# design.net
KiCad netlist of a schematic drawn in EasyEDA Pro
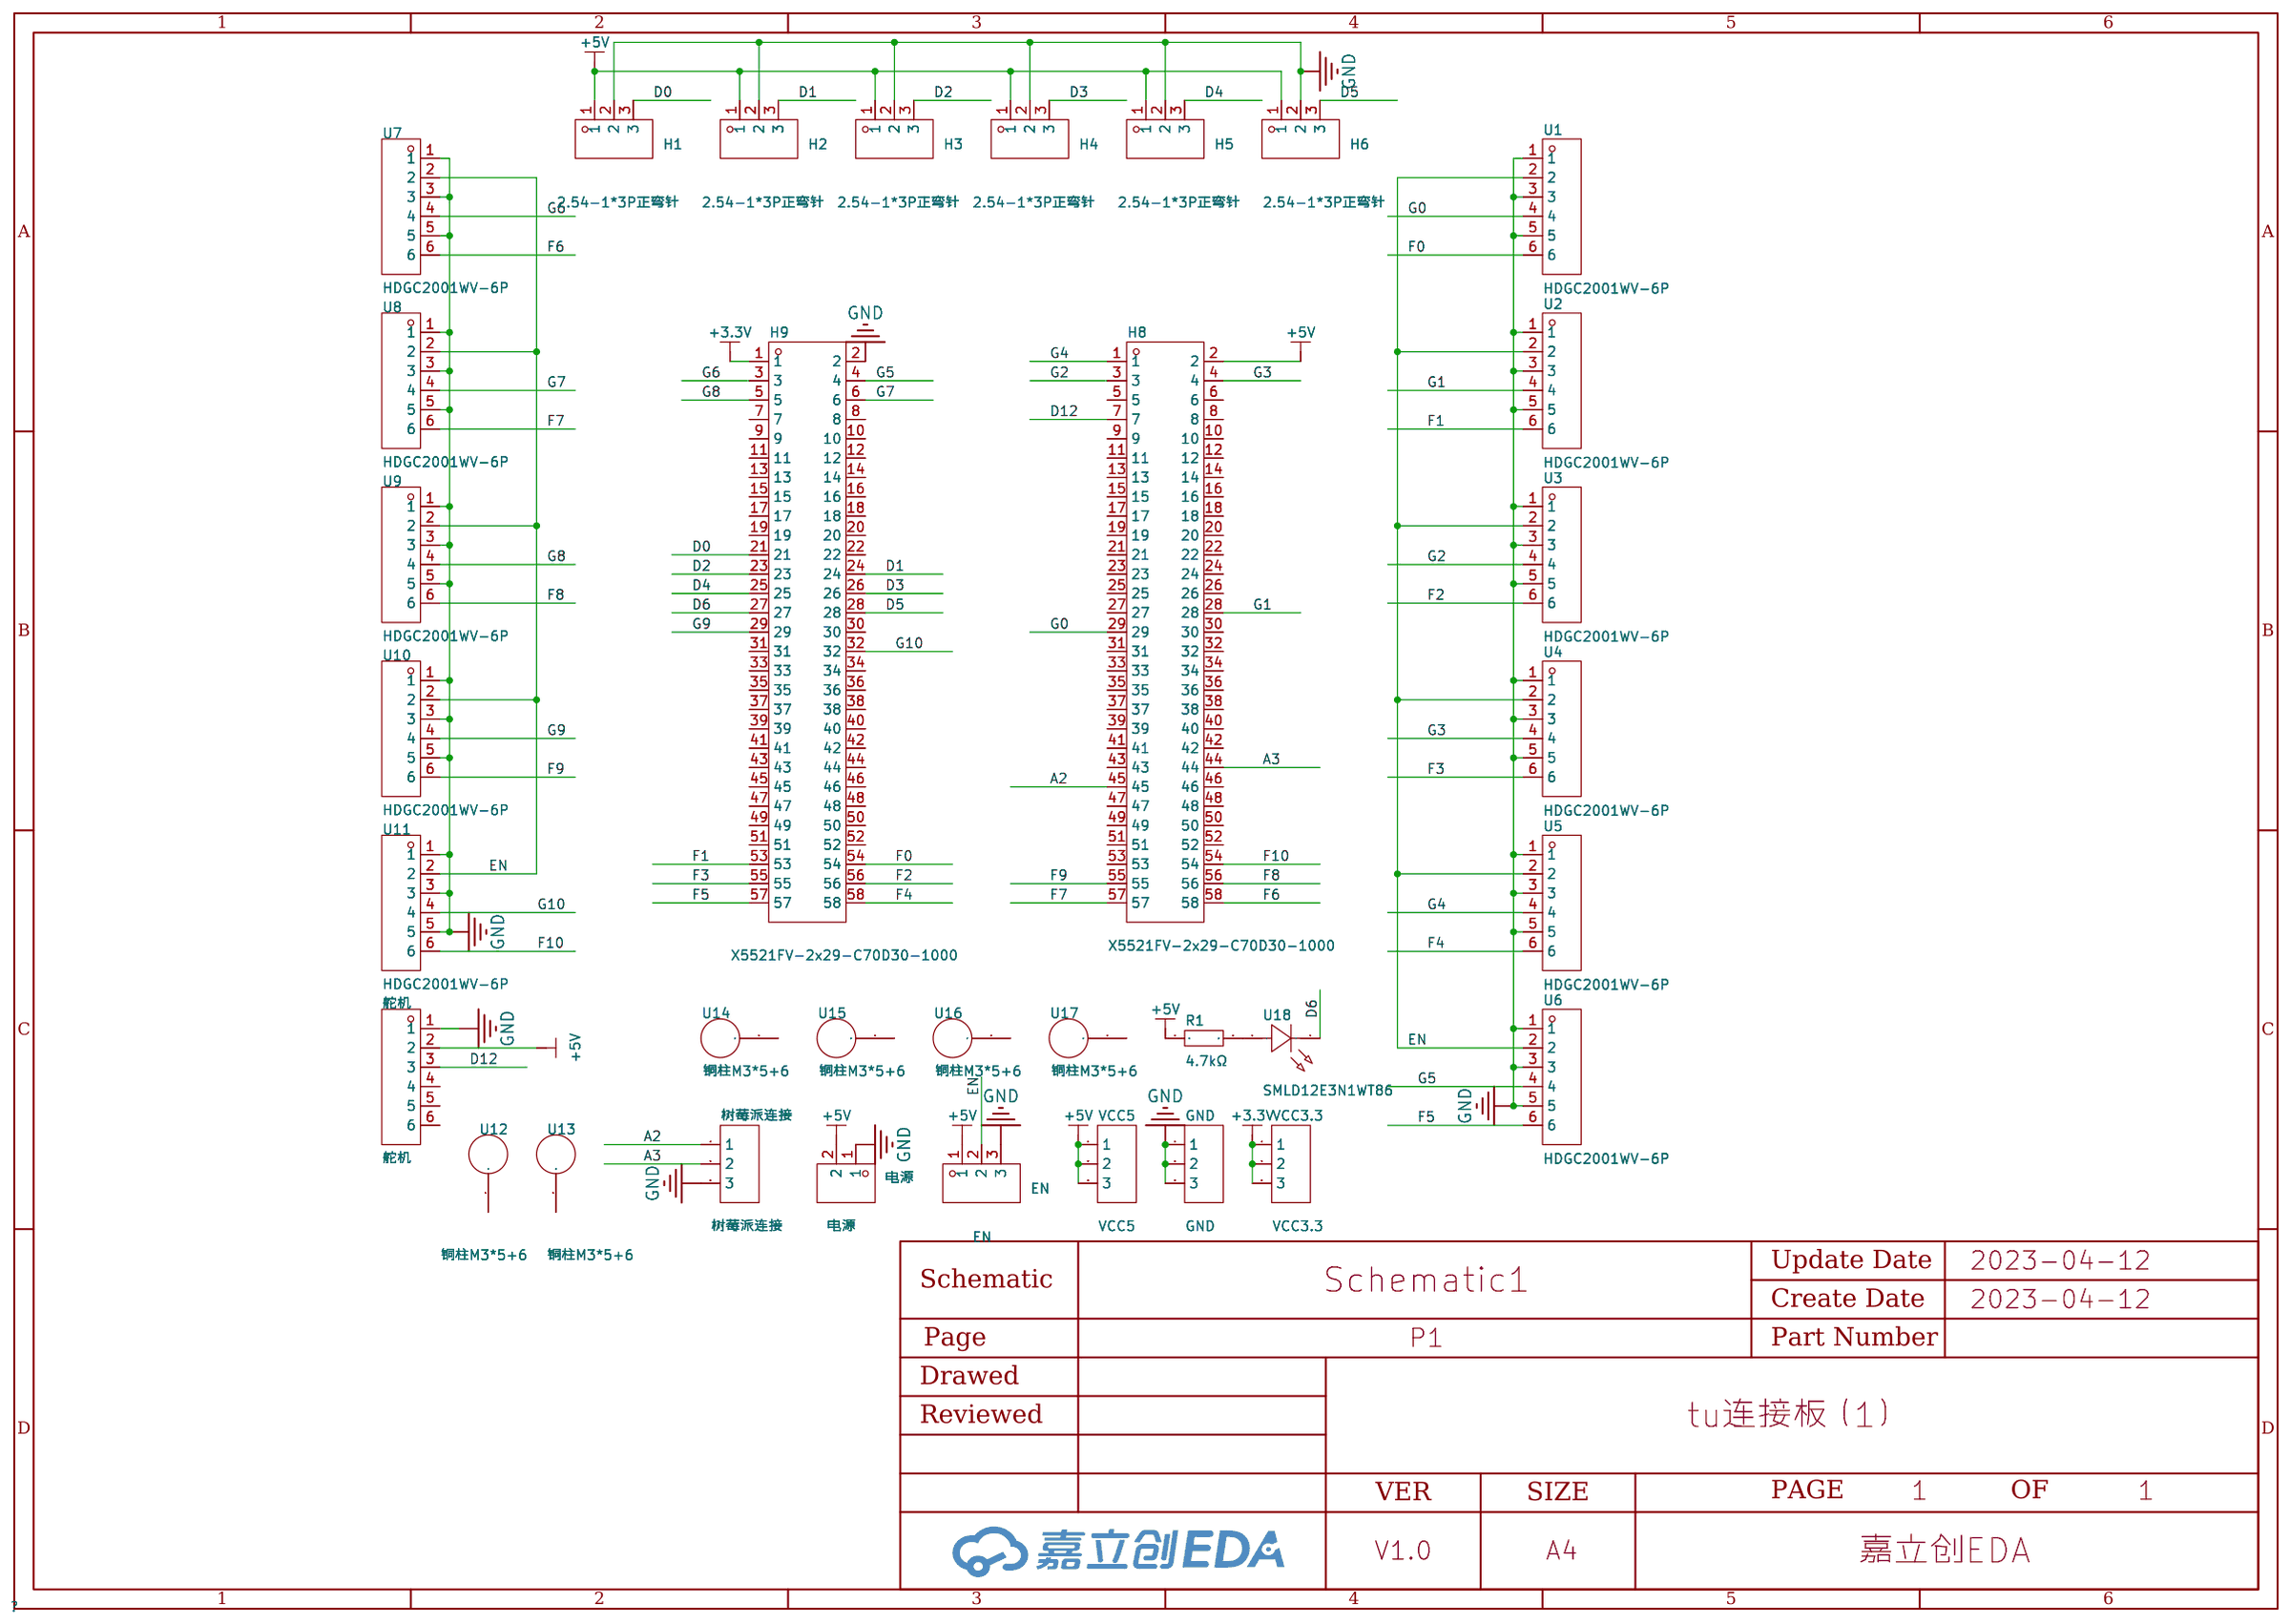
[diagram p0: schematic sheet]

(export (version "E")
  (design (tool "Eeschema 10.0.6"))
  (components
    (comp (ref "EN")
      (value "EN")
      (footprint "easyedapro:HDR-TH_3P-P2.54-H-M-BW7.2-P")
      (fields (field (name "Manufacturer Part") "2.54-1*3P正弯针") (field (name "Manufacturer") "BOOMELE(博穆精密)"))
      (libsource (lib "easyedapro") (part "C92159"))
    )
    (comp (ref "GND")
      (value "GND")
      (footprint "easyedapro:HDR-TH_3P-P2.54-V-M-1")
      (fields (field (name "Manufacturer Part") "2.54-1*3P针") (field (name "Manufacturer") "BOOMELE(博穆精密)"))
      (libsource (lib "easyedapro") (part "Header-Male-2.54_1x3"))
    )
    (comp (ref "H1")
      (value "2.54-1*3P正弯针")
      (footprint "easyedapro:HDR-TH_3P-P2.54-H-M-BW7.2-P")
      (fields (field (name "Manufacturer") "BOOMELE(博穆精密)"))
      (libsource (lib "easyedapro") (part "C92159"))
    )
    (comp (ref "H2")
      (value "2.54-1*3P正弯针")
      (footprint "easyedapro:HDR-TH_3P-P2.54-H-M-BW7.2-P")
      (fields (field (name "Manufacturer") "BOOMELE(博穆精密)"))
      (libsource (lib "easyedapro") (part "C92159"))
    )
    (comp (ref "H3")
      (value "2.54-1*3P正弯针")
      (footprint "easyedapro:HDR-TH_3P-P2.54-H-M-BW7.2-P")
      (fields (field (name "Manufacturer") "BOOMELE(博穆精密)"))
      (libsource (lib "easyedapro") (part "C92159"))
    )
    (comp (ref "H4")
      (value "2.54-1*3P正弯针")
      (footprint "easyedapro:HDR-TH_3P-P2.54-H-M-BW7.2-P")
      (fields (field (name "Manufacturer") "BOOMELE(博穆精密)"))
      (libsource (lib "easyedapro") (part "C92159"))
    )
    (comp (ref "H5")
      (value "2.54-1*3P正弯针")
      (footprint "easyedapro:HDR-TH_3P-P2.54-H-M-BW7.2-P")
      (fields (field (name "Manufacturer") "BOOMELE(博穆精密)"))
      (libsource (lib "easyedapro") (part "C92159"))
    )
    (comp (ref "H6")
      (value "2.54-1*3P正弯针")
      (footprint "easyedapro:HDR-TH_3P-P2.54-H-M-BW7.2-P")
      (fields (field (name "Manufacturer") "BOOMELE(博穆精密)"))
      (libsource (lib "easyedapro") (part "C92159"))
    )
    (comp (ref "H8")
      (value "X5521FV-2x29-C70D30-1000")
      (footprint "easyedapro:HDR-TH_58P-P2.54-V-F-R2-C29-S2.54")
      (fields (field (name "Manufacturer") "XKB Connectivity(中国星坤)"))
      (libsource (lib "easyedapro") (part "X5521FV-2X29-C70D30-1000"))
    )
    (comp (ref "H9")
      (value "X5521FV-2x29-C70D30-1000")
      (footprint "easyedapro:HDR-TH_58P-P2.54-V-F-R2-C29-S2.54")
      (fields (field (name "Manufacturer") "XKB Connectivity(中国星坤)"))
      (libsource (lib "easyedapro") (part "X5521FV-2X29-C70D30-1000"))
    )
    (comp (ref "R1")
      (value "4.7kΩ")
      (footprint "easyedapro:R0603")
      (description "电阻类型:厚膜电阻;阻值:10kΩ;精度:±1%;功率:100mW;")
      (fields
        (field (name "Manufacturer Part") "0603WAF1002T5E")
        (field (name "Manufacturer") "UNI-ROYAL(厚声)")
      )
      (libsource (lib "easyedapro") (part "0603WAF1002T5E"))
    )
    (comp (ref "U1")
      (value "HDGC2001WV-6P")
      (footprint "easyedapro:CONN-TH_6P-P2.00_HDGC2001WV-6P")
      (fields (field (name "Manufacturer") "HDGC(华德共创)"))
      (libsource (lib "easyedapro") (part "HDGC2001WV-6P"))
    )
    (comp (ref "U2")
      (value "HDGC2001WV-6P")
      (footprint "easyedapro:CONN-TH_6P-P2.00_HDGC2001WV-6P")
      (fields (field (name "Manufacturer") "HDGC(华德共创)"))
      (libsource (lib "easyedapro") (part "HDGC2001WV-6P"))
    )
    (comp (ref "U3")
      (value "HDGC2001WV-6P")
      (footprint "easyedapro:CONN-TH_6P-P2.00_HDGC2001WV-6P")
      (fields (field (name "Manufacturer") "HDGC(华德共创)"))
      (libsource (lib "easyedapro") (part "HDGC2001WV-6P"))
    )
    (comp (ref "U4")
      (value "HDGC2001WV-6P")
      (footprint "easyedapro:CONN-TH_6P-P2.00_HDGC2001WV-6P")
      (fields (field (name "Manufacturer") "HDGC(华德共创)"))
      (libsource (lib "easyedapro") (part "HDGC2001WV-6P"))
    )
    (comp (ref "U5")
      (value "HDGC2001WV-6P")
      (footprint "easyedapro:CONN-TH_6P-P2.00_HDGC2001WV-6P")
      (fields (field (name "Manufacturer") "HDGC(华德共创)"))
      (libsource (lib "easyedapro") (part "HDGC2001WV-6P"))
    )
    (comp (ref "U6")
      (value "HDGC2001WV-6P")
      (footprint "easyedapro:CONN-TH_6P-P2.00_HDGC2001WV-6P")
      (fields (field (name "Manufacturer") "HDGC(华德共创)"))
      (libsource (lib "easyedapro") (part "HDGC2001WV-6P"))
    )
    (comp (ref "U7")
      (value "HDGC2001WV-6P")
      (footprint "easyedapro:CONN-TH_6P-P2.00_HDGC2001WV-6P")
      (fields (field (name "Manufacturer") "HDGC(华德共创)"))
      (libsource (lib "easyedapro") (part "HDGC2001WV-6P"))
    )
    (comp (ref "U8")
      (value "HDGC2001WV-6P")
      (footprint "easyedapro:CONN-TH_6P-P2.00_HDGC2001WV-6P")
      (fields (field (name "Manufacturer") "HDGC(华德共创)"))
      (libsource (lib "easyedapro") (part "HDGC2001WV-6P"))
    )
    (comp (ref "U9")
      (value "HDGC2001WV-6P")
      (footprint "easyedapro:CONN-TH_6P-P2.00_HDGC2001WV-6P")
      (fields (field (name "Manufacturer") "HDGC(华德共创)"))
      (libsource (lib "easyedapro") (part "HDGC2001WV-6P"))
    )
    (comp (ref "U10")
      (value "HDGC2001WV-6P")
      (footprint "easyedapro:CONN-TH_6P-P2.00_HDGC2001WV-6P")
      (fields (field (name "Manufacturer") "HDGC(华德共创)"))
      (libsource (lib "easyedapro") (part "HDGC2001WV-6P"))
    )
    (comp (ref "U11")
      (value "HDGC2001WV-6P")
      (footprint "easyedapro:CONN-TH_6P-P2.00_HDGC2001WV-6P")
      (fields (field (name "Manufacturer") "HDGC(华德共创)"))
      (libsource (lib "easyedapro") (part "HDGC2001WV-6P"))
    )
    (comp (ref "U12")
      (value "铜柱M3*5+6")
      (footprint "easyedapro:SMD_BD4.2-L4.7-W4.7-D3.0")
      (description "螺柱类型:单通螺柱;公称直径:M3;螺距:-;长度:11mm;执行标准:-;强度等级:-;材料:-;表面处理:-;")
      (fields (field (name "Manufacturer") "国产"))
      (libsource (lib "easyedapro") (part "铜柱M3*5+6"))
    )
    (comp (ref "U13")
      (value "铜柱M3*5+6")
      (footprint "easyedapro:SMD_BD4.2-L4.7-W4.7-D3.0")
      (description "螺柱类型:单通螺柱;公称直径:M3;螺距:-;长度:11mm;执行标准:-;强度等级:-;材料:-;表面处理:-;")
      (fields (field (name "Manufacturer") "国产"))
      (libsource (lib "easyedapro") (part "铜柱M3*5+6"))
    )
    (comp (ref "U14")
      (value "铜柱M3*5+6")
      (footprint "easyedapro:SMD_BD4.2-L4.7-W4.7-D3.0")
      (description "螺柱类型:单通螺柱;公称直径:M3;螺距:-;长度:11mm;执行标准:-;强度等级:-;材料:-;表面处理:-;")
      (fields (field (name "Manufacturer") "国产"))
      (libsource (lib "easyedapro") (part "铜柱M3*5+6"))
    )
    (comp (ref "U15")
      (value "铜柱M3*5+6")
      (footprint "easyedapro:SMD_BD4.2-L4.7-W4.7-D3.0")
      (description "螺柱类型:单通螺柱;公称直径:M3;螺距:-;长度:11mm;执行标准:-;强度等级:-;材料:-;表面处理:-;")
      (fields (field (name "Manufacturer") "国产"))
      (libsource (lib "easyedapro") (part "铜柱M3*5+6"))
    )
    (comp (ref "U16")
      (value "铜柱M3*5+6")
      (footprint "easyedapro:SMD_BD4.2-L4.7-W4.7-D3.0")
      (description "螺柱类型:单通螺柱;公称直径:M3;螺距:-;长度:11mm;执行标准:-;强度等级:-;材料:-;表面处理:-;")
      (fields (field (name "Manufacturer") "国产"))
      (libsource (lib "easyedapro") (part "铜柱M3*5+6"))
    )
    (comp (ref "U17")
      (value "铜柱M3*5+6")
      (footprint "easyedapro:SMD_BD4.2-L4.7-W4.7-D3.0")
      (description "螺柱类型:单通螺柱;公称直径:M3;螺距:-;长度:11mm;执行标准:-;强度等级:-;材料:-;表面处理:-;")
      (fields (field (name "Manufacturer") "国产"))
      (libsource (lib "easyedapro") (part "铜柱M3*5+6"))
    )
    (comp (ref "U18")
      (value "SMLD12E3N1WT86")
      (footprint "easyedapro:LED-SMD_L1.6-W0.8-RD")
      (fields (field (name "Manufacturer") "ROHM(罗姆)"))
      (libsource (lib "easyedapro") (part "SMLD12E3N1WT86"))
    )
    (comp (ref "VCC3.3")
      (value "VCC3.3")
      (footprint "easyedapro:HDR-TH_3P-P2.54-V-M-1")
      (fields (field (name "Manufacturer Part") "2.54-1*3P针") (field (name "Manufacturer") "BOOMELE(博穆精密)"))
      (libsource (lib "easyedapro") (part "Header-Male-2.54_1x3"))
    )
    (comp (ref "VCC5")
      (value "VCC5")
      (footprint "easyedapro:HDR-TH_3P-P2.54-V-M-1")
      (fields (field (name "Manufacturer Part") "2.54-1*3P针") (field (name "Manufacturer") "BOOMELE(博穆精密)"))
      (libsource (lib "easyedapro") (part "Header-Male-2.54_1x3"))
    )
    (comp (ref "树莓派连接")
      (value "树莓派连接")
      (footprint "easyedapro:HDR-TH_3P-P2.54-V-M-1")
      (fields (field (name "Manufacturer Part") "2.54-1*3P针") (field (name "Manufacturer") "BOOMELE(博穆精密)"))
      (libsource (lib "easyedapro") (part "Header-Male-2.54_1x3"))
    )
    (comp (ref "电源")
      (value "电源")
      (footprint "easyedapro:CONN-TH_XHB-2A_C2829622")
      (fields (field (name "Manufacturer Part") "XHB-2A") (field (name "Manufacturer") "FG(富港)"))
      (libsource (lib "easyedapro") (part "XHB-2A_C2829622"))
    )
    (comp (ref "舵机")
      (value "舵机")
      (footprint "easyedapro:CONN-TH_6P-P2.00_HDGC2001WV-6P")
      (fields (field (name "Manufacturer Part") "HDGC2001WV-6P") (field (name "Manufacturer") "HDGC(华德共创)"))
      (libsource (lib "easyedapro") (part "HDGC2001WV-6P"))
    )
  )
  (nets
    (net (code "1") (name "+3.3V") (class "Default")
      (node (ref "H9") (pin "1") (pinfunction "1_1") (pintype "input"))
      (node (ref "VCC3.3") (pin "1") (pinfunction "1_1") (pintype "input"))
      (node (ref "VCC3.3") (pin "2") (pinfunction "2_2") (pintype "input"))
      (node (ref "VCC3.3") (pin "3") (pinfunction "3_3") (pintype "input"))
    )
    (net (code "2") (name "+5V") (class "Default")
      (node (ref "EN") (pin "1") (pinfunction "1_1") (pintype "input"))
      (node (ref "H1") (pin "1") (pinfunction "1_1") (pintype "input"))
      (node (ref "H2") (pin "1") (pinfunction "1_1") (pintype "input"))
      (node (ref "H3") (pin "1") (pinfunction "1_1") (pintype "input"))
      (node (ref "H4") (pin "1") (pinfunction "1_1") (pintype "input"))
      (node (ref "H5") (pin "1") (pinfunction "1_1") (pintype "input"))
      (node (ref "H6") (pin "1") (pinfunction "1_1") (pintype "input"))
      (node (ref "H8") (pin "2") (pinfunction "2_2") (pintype "input"))
      (node (ref "R1") (pin "1") (pinfunction "1_1") (pintype "input"))
      (node (ref "VCC5") (pin "1") (pinfunction "1_1") (pintype "input"))
      (node (ref "VCC5") (pin "2") (pinfunction "2_2") (pintype "input"))
      (node (ref "VCC5") (pin "3") (pinfunction "3_3") (pintype "input"))
      (node (ref "电源") (pin "2") (pinfunction "2_2") (pintype "input"))
      (node (ref "舵机") (pin "2") (pinfunction "2_2") (pintype "input"))
    )
    (net (code "3") (name "/A2") (class "Default")
      (node (ref "H8") (pin "45") (pinfunction "45_45") (pintype "input"))
      (node (ref "树莓派连接") (pin "1") (pinfunction "1_1") (pintype "input"))
    )
    (net (code "4") (name "/A3") (class "Default")
      (node (ref "H8") (pin "44") (pinfunction "44_44") (pintype "input"))
      (node (ref "树莓派连接") (pin "2") (pinfunction "2_2") (pintype "input"))
    )
    (net (code "5") (name "/D0") (class "Default")
      (node (ref "H1") (pin "3") (pinfunction "3_3") (pintype "input"))
      (node (ref "H9") (pin "21") (pinfunction "21_21") (pintype "input"))
    )
    (net (code "6") (name "/D1") (class "Default")
      (node (ref "H2") (pin "3") (pinfunction "3_3") (pintype "input"))
      (node (ref "H9") (pin "24") (pinfunction "24_24") (pintype "input"))
    )
    (net (code "7") (name "/D2") (class "Default")
      (node (ref "H3") (pin "3") (pinfunction "3_3") (pintype "input"))
      (node (ref "H9") (pin "23") (pinfunction "23_23") (pintype "input"))
    )
    (net (code "8") (name "/D3") (class "Default")
      (node (ref "H4") (pin "3") (pinfunction "3_3") (pintype "input"))
      (node (ref "H9") (pin "26") (pinfunction "26_26") (pintype "input"))
    )
    (net (code "9") (name "/D4") (class "Default")
      (node (ref "H5") (pin "3") (pinfunction "3_3") (pintype "input"))
      (node (ref "H9") (pin "25") (pinfunction "25_25") (pintype "input"))
    )
    (net (code "10") (name "/D5") (class "Default")
      (node (ref "H6") (pin "3") (pinfunction "3_3") (pintype "input"))
      (node (ref "H9") (pin "28") (pinfunction "28_28") (pintype "input"))
    )
    (net (code "11") (name "/D6") (class "Default")
      (node (ref "H9") (pin "27") (pinfunction "27_27") (pintype "input"))
      (node (ref "U18") (pin "1") (pinfunction "-_1") (pintype "input"))
    )
    (net (code "12") (name "/D12") (class "Default")
      (node (ref "H8") (pin "7") (pinfunction "7_7") (pintype "input"))
      (node (ref "舵机") (pin "3") (pinfunction "3_3") (pintype "input"))
    )
    (net (code "13") (name "/EN") (class "Default")
      (node (ref "EN") (pin "2") (pinfunction "2_2") (pintype "input"))
      (node (ref "U1") (pin "2") (pinfunction "2_2") (pintype "input"))
      (node (ref "U10") (pin "2") (pinfunction "2_2") (pintype "input"))
      (node (ref "U11") (pin "2") (pinfunction "2_2") (pintype "input"))
      (node (ref "U2") (pin "2") (pinfunction "2_2") (pintype "input"))
      (node (ref "U3") (pin "2") (pinfunction "2_2") (pintype "input"))
      (node (ref "U4") (pin "2") (pinfunction "2_2") (pintype "input"))
      (node (ref "U5") (pin "2") (pinfunction "2_2") (pintype "input"))
      (node (ref "U6") (pin "2") (pinfunction "2_2") (pintype "input"))
      (node (ref "U7") (pin "2") (pinfunction "2_2") (pintype "input"))
      (node (ref "U8") (pin "2") (pinfunction "2_2") (pintype "input"))
      (node (ref "U9") (pin "2") (pinfunction "2_2") (pintype "input"))
    )
    (net (code "14") (name "/F0") (class "Default")
      (node (ref "H9") (pin "54") (pinfunction "54_54") (pintype "input"))
      (node (ref "U1") (pin "6") (pinfunction "6_6") (pintype "input"))
    )
    (net (code "15") (name "/F1") (class "Default")
      (node (ref "H9") (pin "53") (pinfunction "53_53") (pintype "input"))
      (node (ref "U2") (pin "6") (pinfunction "6_6") (pintype "input"))
    )
    (net (code "16") (name "/F2") (class "Default")
      (node (ref "H9") (pin "56") (pinfunction "56_56") (pintype "input"))
      (node (ref "U3") (pin "6") (pinfunction "6_6") (pintype "input"))
    )
    (net (code "17") (name "/F3") (class "Default")
      (node (ref "H9") (pin "55") (pinfunction "55_55") (pintype "input"))
      (node (ref "U4") (pin "6") (pinfunction "6_6") (pintype "input"))
    )
    (net (code "18") (name "/F4") (class "Default")
      (node (ref "H9") (pin "58") (pinfunction "58_58") (pintype "input"))
      (node (ref "U5") (pin "6") (pinfunction "6_6") (pintype "input"))
    )
    (net (code "19") (name "/F5") (class "Default")
      (node (ref "H9") (pin "57") (pinfunction "57_57") (pintype "input"))
      (node (ref "U6") (pin "6") (pinfunction "6_6") (pintype "input"))
    )
    (net (code "20") (name "/F6") (class "Default")
      (node (ref "H8") (pin "58") (pinfunction "58_58") (pintype "input"))
      (node (ref "U7") (pin "6") (pinfunction "6_6") (pintype "input"))
    )
    (net (code "21") (name "/F7") (class "Default")
      (node (ref "H8") (pin "57") (pinfunction "57_57") (pintype "input"))
      (node (ref "U8") (pin "6") (pinfunction "6_6") (pintype "input"))
    )
    (net (code "22") (name "/F8") (class "Default")
      (node (ref "H8") (pin "56") (pinfunction "56_56") (pintype "input"))
      (node (ref "U9") (pin "6") (pinfunction "6_6") (pintype "input"))
    )
    (net (code "23") (name "/F9") (class "Default")
      (node (ref "H8") (pin "55") (pinfunction "55_55") (pintype "input"))
      (node (ref "U10") (pin "6") (pinfunction "6_6") (pintype "input"))
    )
    (net (code "24") (name "/F10") (class "Default")
      (node (ref "H8") (pin "54") (pinfunction "54_54") (pintype "input"))
      (node (ref "U11") (pin "6") (pinfunction "6_6") (pintype "input"))
    )
    (net (code "25") (name "/G0") (class "Default")
      (node (ref "H8") (pin "29") (pinfunction "29_29") (pintype "input"))
      (node (ref "U1") (pin "4") (pinfunction "4_4") (pintype "input"))
    )
    (net (code "26") (name "/G1") (class "Default")
      (node (ref "H8") (pin "28") (pinfunction "28_28") (pintype "input"))
      (node (ref "U2") (pin "4") (pinfunction "4_4") (pintype "input"))
    )
    (net (code "27") (name "/G2") (class "Default")
      (node (ref "H8") (pin "3") (pinfunction "3_3") (pintype "input"))
      (node (ref "U3") (pin "4") (pinfunction "4_4") (pintype "input"))
    )
    (net (code "28") (name "/G3") (class "Default")
      (node (ref "H8") (pin "4") (pinfunction "4_4") (pintype "input"))
      (node (ref "U4") (pin "4") (pinfunction "4_4") (pintype "input"))
    )
    (net (code "29") (name "/G4") (class "Default")
      (node (ref "H8") (pin "1") (pinfunction "1_1") (pintype "input"))
      (node (ref "U5") (pin "4") (pinfunction "4_4") (pintype "input"))
    )
    (net (code "30") (name "/G5") (class "Default")
      (node (ref "H9") (pin "4") (pinfunction "4_4") (pintype "input"))
      (node (ref "U6") (pin "4") (pinfunction "4_4") (pintype "input"))
    )
    (net (code "31") (name "/G6") (class "Default")
      (node (ref "H9") (pin "3") (pinfunction "3_3") (pintype "input"))
      (node (ref "U7") (pin "4") (pinfunction "4_4") (pintype "input"))
    )
    (net (code "32") (name "/G7") (class "Default")
      (node (ref "H9") (pin "6") (pinfunction "6_6") (pintype "input"))
      (node (ref "U8") (pin "4") (pinfunction "4_4") (pintype "input"))
    )
    (net (code "33") (name "/G8") (class "Default")
      (node (ref "H9") (pin "5") (pinfunction "5_5") (pintype "input"))
      (node (ref "U9") (pin "4") (pinfunction "4_4") (pintype "input"))
    )
    (net (code "34") (name "/G9") (class "Default")
      (node (ref "H9") (pin "29") (pinfunction "29_29") (pintype "input"))
      (node (ref "U10") (pin "4") (pinfunction "4_4") (pintype "input"))
    )
    (net (code "35") (name "/G10") (class "Default")
      (node (ref "H9") (pin "32") (pinfunction "32_32") (pintype "input"))
      (node (ref "U11") (pin "4") (pinfunction "4_4") (pintype "input"))
    )
    (net (code "36") (name "GND") (class "Default")
      (node (ref "EN") (pin "3") (pinfunction "3_3") (pintype "input"))
      (node (ref "GND") (pin "1") (pinfunction "1_1") (pintype "input"))
      (node (ref "GND") (pin "2") (pinfunction "2_2") (pintype "input"))
      (node (ref "GND") (pin "3") (pinfunction "3_3") (pintype "input"))
      (node (ref "H1") (pin "2") (pinfunction "2_2") (pintype "input"))
      (node (ref "H2") (pin "2") (pinfunction "2_2") (pintype "input"))
      (node (ref "H3") (pin "2") (pinfunction "2_2") (pintype "input"))
      (node (ref "H4") (pin "2") (pinfunction "2_2") (pintype "input"))
      (node (ref "H5") (pin "2") (pinfunction "2_2") (pintype "input"))
      (node (ref "H6") (pin "2") (pinfunction "2_2") (pintype "input"))
      (node (ref "H9") (pin "2") (pinfunction "2_2") (pintype "input"))
      (node (ref "U1") (pin "1") (pinfunction "1_1") (pintype "input"))
      (node (ref "U1") (pin "3") (pinfunction "3_3") (pintype "input"))
      (node (ref "U1") (pin "5") (pinfunction "5_5") (pintype "input"))
      (node (ref "U10") (pin "1") (pinfunction "1_1") (pintype "input"))
      (node (ref "U10") (pin "3") (pinfunction "3_3") (pintype "input"))
      (node (ref "U10") (pin "5") (pinfunction "5_5") (pintype "input"))
      (node (ref "U11") (pin "1") (pinfunction "1_1") (pintype "input"))
      (node (ref "U11") (pin "3") (pinfunction "3_3") (pintype "input"))
      (node (ref "U11") (pin "5") (pinfunction "5_5") (pintype "input"))
      (node (ref "U2") (pin "1") (pinfunction "1_1") (pintype "input"))
      (node (ref "U2") (pin "3") (pinfunction "3_3") (pintype "input"))
      (node (ref "U2") (pin "5") (pinfunction "5_5") (pintype "input"))
      (node (ref "U3") (pin "1") (pinfunction "1_1") (pintype "input"))
      (node (ref "U3") (pin "3") (pinfunction "3_3") (pintype "input"))
      (node (ref "U3") (pin "5") (pinfunction "5_5") (pintype "input"))
      (node (ref "U4") (pin "1") (pinfunction "1_1") (pintype "input"))
      (node (ref "U4") (pin "3") (pinfunction "3_3") (pintype "input"))
      (node (ref "U4") (pin "5") (pinfunction "5_5") (pintype "input"))
      (node (ref "U5") (pin "1") (pinfunction "1_1") (pintype "input"))
      (node (ref "U5") (pin "3") (pinfunction "3_3") (pintype "input"))
      (node (ref "U5") (pin "5") (pinfunction "5_5") (pintype "input"))
      (node (ref "U6") (pin "1") (pinfunction "1_1") (pintype "input"))
      (node (ref "U6") (pin "3") (pinfunction "3_3") (pintype "input"))
      (node (ref "U6") (pin "5") (pinfunction "5_5") (pintype "input"))
      (node (ref "U7") (pin "1") (pinfunction "1_1") (pintype "input"))
      (node (ref "U7") (pin "3") (pinfunction "3_3") (pintype "input"))
      (node (ref "U7") (pin "5") (pinfunction "5_5") (pintype "input"))
      (node (ref "U8") (pin "1") (pinfunction "1_1") (pintype "input"))
      (node (ref "U8") (pin "3") (pinfunction "3_3") (pintype "input"))
      (node (ref "U8") (pin "5") (pinfunction "5_5") (pintype "input"))
      (node (ref "U9") (pin "1") (pinfunction "1_1") (pintype "input"))
      (node (ref "U9") (pin "3") (pinfunction "3_3") (pintype "input"))
      (node (ref "U9") (pin "5") (pinfunction "5_5") (pintype "input"))
      (node (ref "树莓派连接") (pin "3") (pinfunction "3_3") (pintype "input"))
      (node (ref "电源") (pin "1") (pinfunction "1_1") (pintype "input"))
      (node (ref "舵机") (pin "1") (pinfunction "1_1") (pintype "input"))
    )
    (net (code "37") (name "Net-(U18-+)") (class "Default")
      (node (ref "R1") (pin "2") (pinfunction "2_2") (pintype "input"))
      (node (ref "U18") (pin "2") (pinfunction "+_2") (pintype "input"))
    )
    (net (code "38") (name "unconnected-(H8-Pad5)") (class "Default")
      (node (ref "H8") (pin "5") (pinfunction "5_5") (pintype "input"))
    )
    (net (code "39") (name "unconnected-(H8-Pad6)") (class "Default")
      (node (ref "H8") (pin "6") (pinfunction "6_6") (pintype "input"))
    )
    (net (code "40") (name "unconnected-(H8-Pad8)") (class "Default")
      (node (ref "H8") (pin "8") (pinfunction "8_8") (pintype "input"))
    )
    (net (code "41") (name "unconnected-(H8-Pad9)") (class "Default")
      (node (ref "H8") (pin "9") (pinfunction "9_9") (pintype "input"))
    )
    (net (code "42") (name "unconnected-(H8-Pad10)") (class "Default")
      (node (ref "H8") (pin "10") (pinfunction "10_10") (pintype "input"))
    )
    (net (code "43") (name "unconnected-(H8-Pad11)") (class "Default")
      (node (ref "H8") (pin "11") (pinfunction "11_11") (pintype "input"))
    )
    (net (code "44") (name "unconnected-(H8-Pad12)") (class "Default")
      (node (ref "H8") (pin "12") (pinfunction "12_12") (pintype "input"))
    )
    (net (code "45") (name "unconnected-(H8-Pad13)") (class "Default")
      (node (ref "H8") (pin "13") (pinfunction "13_13") (pintype "input"))
    )
    (net (code "46") (name "unconnected-(H8-Pad14)") (class "Default")
      (node (ref "H8") (pin "14") (pinfunction "14_14") (pintype "input"))
    )
    (net (code "47") (name "unconnected-(H8-Pad15)") (class "Default")
      (node (ref "H8") (pin "15") (pinfunction "15_15") (pintype "input"))
    )
    (net (code "48") (name "unconnected-(H8-Pad16)") (class "Default")
      (node (ref "H8") (pin "16") (pinfunction "16_16") (pintype "input"))
    )
    (net (code "49") (name "unconnected-(H8-Pad17)") (class "Default")
      (node (ref "H8") (pin "17") (pinfunction "17_17") (pintype "input"))
    )
    (net (code "50") (name "unconnected-(H8-Pad18)") (class "Default")
      (node (ref "H8") (pin "18") (pinfunction "18_18") (pintype "input"))
    )
    (net (code "51") (name "unconnected-(H8-Pad19)") (class "Default")
      (node (ref "H8") (pin "19") (pinfunction "19_19") (pintype "input"))
    )
    (net (code "52") (name "unconnected-(H8-Pad20)") (class "Default")
      (node (ref "H8") (pin "20") (pinfunction "20_20") (pintype "input"))
    )
    (net (code "53") (name "unconnected-(H8-Pad21)") (class "Default")
      (node (ref "H8") (pin "21") (pinfunction "21_21") (pintype "input"))
    )
    (net (code "54") (name "unconnected-(H8-Pad22)") (class "Default")
      (node (ref "H8") (pin "22") (pinfunction "22_22") (pintype "input"))
    )
    (net (code "55") (name "unconnected-(H8-Pad23)") (class "Default")
      (node (ref "H8") (pin "23") (pinfunction "23_23") (pintype "input"))
    )
    (net (code "56") (name "unconnected-(H8-Pad24)") (class "Default")
      (node (ref "H8") (pin "24") (pinfunction "24_24") (pintype "input"))
    )
    (net (code "57") (name "unconnected-(H8-Pad25)") (class "Default")
      (node (ref "H8") (pin "25") (pinfunction "25_25") (pintype "input"))
    )
    (net (code "58") (name "unconnected-(H8-Pad26)") (class "Default")
      (node (ref "H8") (pin "26") (pinfunction "26_26") (pintype "input"))
    )
    (net (code "59") (name "unconnected-(H8-Pad27)") (class "Default")
      (node (ref "H8") (pin "27") (pinfunction "27_27") (pintype "input"))
    )
    (net (code "60") (name "unconnected-(H8-Pad30)") (class "Default")
      (node (ref "H8") (pin "30") (pinfunction "30_30") (pintype "input"))
    )
    (net (code "61") (name "unconnected-(H8-Pad31)") (class "Default")
      (node (ref "H8") (pin "31") (pinfunction "31_31") (pintype "input"))
    )
    (net (code "62") (name "unconnected-(H8-Pad32)") (class "Default")
      (node (ref "H8") (pin "32") (pinfunction "32_32") (pintype "input"))
    )
    (net (code "63") (name "unconnected-(H8-Pad33)") (class "Default")
      (node (ref "H8") (pin "33") (pinfunction "33_33") (pintype "input"))
    )
    (net (code "64") (name "unconnected-(H8-Pad34)") (class "Default")
      (node (ref "H8") (pin "34") (pinfunction "34_34") (pintype "input"))
    )
    (net (code "65") (name "unconnected-(H8-Pad35)") (class "Default")
      (node (ref "H8") (pin "35") (pinfunction "35_35") (pintype "input"))
    )
    (net (code "66") (name "unconnected-(H8-Pad36)") (class "Default")
      (node (ref "H8") (pin "36") (pinfunction "36_36") (pintype "input"))
    )
    (net (code "67") (name "unconnected-(H8-Pad37)") (class "Default")
      (node (ref "H8") (pin "37") (pinfunction "37_37") (pintype "input"))
    )
    (net (code "68") (name "unconnected-(H8-Pad38)") (class "Default")
      (node (ref "H8") (pin "38") (pinfunction "38_38") (pintype "input"))
    )
    (net (code "69") (name "unconnected-(H8-Pad39)") (class "Default")
      (node (ref "H8") (pin "39") (pinfunction "39_39") (pintype "input"))
    )
    (net (code "70") (name "unconnected-(H8-Pad40)") (class "Default")
      (node (ref "H8") (pin "40") (pinfunction "40_40") (pintype "input"))
    )
    (net (code "71") (name "unconnected-(H8-Pad41)") (class "Default")
      (node (ref "H8") (pin "41") (pinfunction "41_41") (pintype "input"))
    )
    (net (code "72") (name "unconnected-(H8-Pad42)") (class "Default")
      (node (ref "H8") (pin "42") (pinfunction "42_42") (pintype "input"))
    )
    (net (code "73") (name "unconnected-(H8-Pad43)") (class "Default")
      (node (ref "H8") (pin "43") (pinfunction "43_43") (pintype "input"))
    )
    (net (code "74") (name "unconnected-(H8-Pad46)") (class "Default")
      (node (ref "H8") (pin "46") (pinfunction "46_46") (pintype "input"))
    )
    (net (code "75") (name "unconnected-(H8-Pad47)") (class "Default")
      (node (ref "H8") (pin "47") (pinfunction "47_47") (pintype "input"))
    )
    (net (code "76") (name "unconnected-(H8-Pad48)") (class "Default")
      (node (ref "H8") (pin "48") (pinfunction "48_48") (pintype "input"))
    )
    (net (code "77") (name "unconnected-(H8-Pad49)") (class "Default")
      (node (ref "H8") (pin "49") (pinfunction "49_49") (pintype "input"))
    )
    (net (code "78") (name "unconnected-(H8-Pad50)") (class "Default")
      (node (ref "H8") (pin "50") (pinfunction "50_50") (pintype "input"))
    )
    (net (code "79") (name "unconnected-(H8-Pad51)") (class "Default")
      (node (ref "H8") (pin "51") (pinfunction "51_51") (pintype "input"))
    )
    (net (code "80") (name "unconnected-(H8-Pad52)") (class "Default")
      (node (ref "H8") (pin "52") (pinfunction "52_52") (pintype "input"))
    )
    (net (code "81") (name "unconnected-(H8-Pad53)") (class "Default")
      (node (ref "H8") (pin "53") (pinfunction "53_53") (pintype "input"))
    )
    (net (code "82") (name "unconnected-(H9-Pad7)") (class "Default")
      (node (ref "H9") (pin "7") (pinfunction "7_7") (pintype "input"))
    )
    (net (code "83") (name "unconnected-(H9-Pad8)") (class "Default")
      (node (ref "H9") (pin "8") (pinfunction "8_8") (pintype "input"))
    )
    (net (code "84") (name "unconnected-(H9-Pad9)") (class "Default")
      (node (ref "H9") (pin "9") (pinfunction "9_9") (pintype "input"))
    )
    (net (code "85") (name "unconnected-(H9-Pad10)") (class "Default")
      (node (ref "H9") (pin "10") (pinfunction "10_10") (pintype "input"))
    )
    (net (code "86") (name "unconnected-(H9-Pad11)") (class "Default")
      (node (ref "H9") (pin "11") (pinfunction "11_11") (pintype "input"))
    )
    (net (code "87") (name "unconnected-(H9-Pad12)") (class "Default")
      (node (ref "H9") (pin "12") (pinfunction "12_12") (pintype "input"))
    )
    (net (code "88") (name "unconnected-(H9-Pad13)") (class "Default")
      (node (ref "H9") (pin "13") (pinfunction "13_13") (pintype "input"))
    )
    (net (code "89") (name "unconnected-(H9-Pad14)") (class "Default")
      (node (ref "H9") (pin "14") (pinfunction "14_14") (pintype "input"))
    )
    (net (code "90") (name "unconnected-(H9-Pad15)") (class "Default")
      (node (ref "H9") (pin "15") (pinfunction "15_15") (pintype "input"))
    )
    (net (code "91") (name "unconnected-(H9-Pad16)") (class "Default")
      (node (ref "H9") (pin "16") (pinfunction "16_16") (pintype "input"))
    )
    (net (code "92") (name "unconnected-(H9-Pad17)") (class "Default")
      (node (ref "H9") (pin "17") (pinfunction "17_17") (pintype "input"))
    )
    (net (code "93") (name "unconnected-(H9-Pad18)") (class "Default")
      (node (ref "H9") (pin "18") (pinfunction "18_18") (pintype "input"))
    )
    (net (code "94") (name "unconnected-(H9-Pad19)") (class "Default")
      (node (ref "H9") (pin "19") (pinfunction "19_19") (pintype "input"))
    )
    (net (code "95") (name "unconnected-(H9-Pad20)") (class "Default")
      (node (ref "H9") (pin "20") (pinfunction "20_20") (pintype "input"))
    )
    (net (code "96") (name "unconnected-(H9-Pad22)") (class "Default")
      (node (ref "H9") (pin "22") (pinfunction "22_22") (pintype "input"))
    )
    (net (code "97") (name "unconnected-(H9-Pad30)") (class "Default")
      (node (ref "H9") (pin "30") (pinfunction "30_30") (pintype "input"))
    )
    (net (code "98") (name "unconnected-(H9-Pad31)") (class "Default")
      (node (ref "H9") (pin "31") (pinfunction "31_31") (pintype "input"))
    )
    (net (code "99") (name "unconnected-(H9-Pad33)") (class "Default")
      (node (ref "H9") (pin "33") (pinfunction "33_33") (pintype "input"))
    )
    (net (code "100") (name "unconnected-(H9-Pad34)") (class "Default")
      (node (ref "H9") (pin "34") (pinfunction "34_34") (pintype "input"))
    )
    (net (code "101") (name "unconnected-(H9-Pad35)") (class "Default")
      (node (ref "H9") (pin "35") (pinfunction "35_35") (pintype "input"))
    )
    (net (code "102") (name "unconnected-(H9-Pad36)") (class "Default")
      (node (ref "H9") (pin "36") (pinfunction "36_36") (pintype "input"))
    )
    (net (code "103") (name "unconnected-(H9-Pad37)") (class "Default")
      (node (ref "H9") (pin "37") (pinfunction "37_37") (pintype "input"))
    )
    (net (code "104") (name "unconnected-(H9-Pad38)") (class "Default")
      (node (ref "H9") (pin "38") (pinfunction "38_38") (pintype "input"))
    )
    (net (code "105") (name "unconnected-(H9-Pad39)") (class "Default")
      (node (ref "H9") (pin "39") (pinfunction "39_39") (pintype "input"))
    )
    (net (code "106") (name "unconnected-(H9-Pad40)") (class "Default")
      (node (ref "H9") (pin "40") (pinfunction "40_40") (pintype "input"))
    )
    (net (code "107") (name "unconnected-(H9-Pad41)") (class "Default")
      (node (ref "H9") (pin "41") (pinfunction "41_41") (pintype "input"))
    )
    (net (code "108") (name "unconnected-(H9-Pad42)") (class "Default")
      (node (ref "H9") (pin "42") (pinfunction "42_42") (pintype "input"))
    )
    (net (code "109") (name "unconnected-(H9-Pad43)") (class "Default")
      (node (ref "H9") (pin "43") (pinfunction "43_43") (pintype "input"))
    )
    (net (code "110") (name "unconnected-(H9-Pad44)") (class "Default")
      (node (ref "H9") (pin "44") (pinfunction "44_44") (pintype "input"))
    )
    (net (code "111") (name "unconnected-(H9-Pad45)") (class "Default")
      (node (ref "H9") (pin "45") (pinfunction "45_45") (pintype "input"))
    )
    (net (code "112") (name "unconnected-(H9-Pad46)") (class "Default")
      (node (ref "H9") (pin "46") (pinfunction "46_46") (pintype "input"))
    )
    (net (code "113") (name "unconnected-(H9-Pad47)") (class "Default")
      (node (ref "H9") (pin "47") (pinfunction "47_47") (pintype "input"))
    )
    (net (code "114") (name "unconnected-(H9-Pad48)") (class "Default")
      (node (ref "H9") (pin "48") (pinfunction "48_48") (pintype "input"))
    )
    (net (code "115") (name "unconnected-(H9-Pad49)") (class "Default")
      (node (ref "H9") (pin "49") (pinfunction "49_49") (pintype "input"))
    )
    (net (code "116") (name "unconnected-(H9-Pad50)") (class "Default")
      (node (ref "H9") (pin "50") (pinfunction "50_50") (pintype "input"))
    )
    (net (code "117") (name "unconnected-(H9-Pad51)") (class "Default")
      (node (ref "H9") (pin "51") (pinfunction "51_51") (pintype "input"))
    )
    (net (code "118") (name "unconnected-(H9-Pad52)") (class "Default")
      (node (ref "H9") (pin "52") (pinfunction "52_52") (pintype "input"))
    )
    (net (code "119") (name "unconnected-(U12-Pad1)") (class "Default")
      (node (ref "U12") (pin "1") (pinfunction "1_1") (pintype "input"))
    )
    (net (code "120") (name "unconnected-(U13-Pad1)") (class "Default")
      (node (ref "U13") (pin "1") (pinfunction "1_1") (pintype "input"))
    )
    (net (code "121") (name "unconnected-(U14-Pad1)") (class "Default")
      (node (ref "U14") (pin "1") (pinfunction "1_1") (pintype "input"))
    )
    (net (code "122") (name "unconnected-(U15-Pad1)") (class "Default")
      (node (ref "U15") (pin "1") (pinfunction "1_1") (pintype "input"))
    )
    (net (code "123") (name "unconnected-(U16-Pad1)") (class "Default")
      (node (ref "U16") (pin "1") (pinfunction "1_1") (pintype "input"))
    )
    (net (code "124") (name "unconnected-(U17-Pad1)") (class "Default")
      (node (ref "U17") (pin "1") (pinfunction "1_1") (pintype "input"))
    )
    (net (code "125") (name "unconnected-(舵机-Pad4)") (class "Default")
      (node (ref "舵机") (pin "4") (pinfunction "4_4") (pintype "input"))
    )
    (net (code "126") (name "unconnected-(舵机-Pad5)") (class "Default")
      (node (ref "舵机") (pin "5") (pinfunction "5_5") (pintype "input"))
    )
    (net (code "127") (name "unconnected-(舵机-Pad6)") (class "Default")
      (node (ref "舵机") (pin "6") (pinfunction "6_6") (pintype "input"))
    )
  )
)
